# multi-level_converter.net
KiCad netlist of a schematic drawn in EAGLE
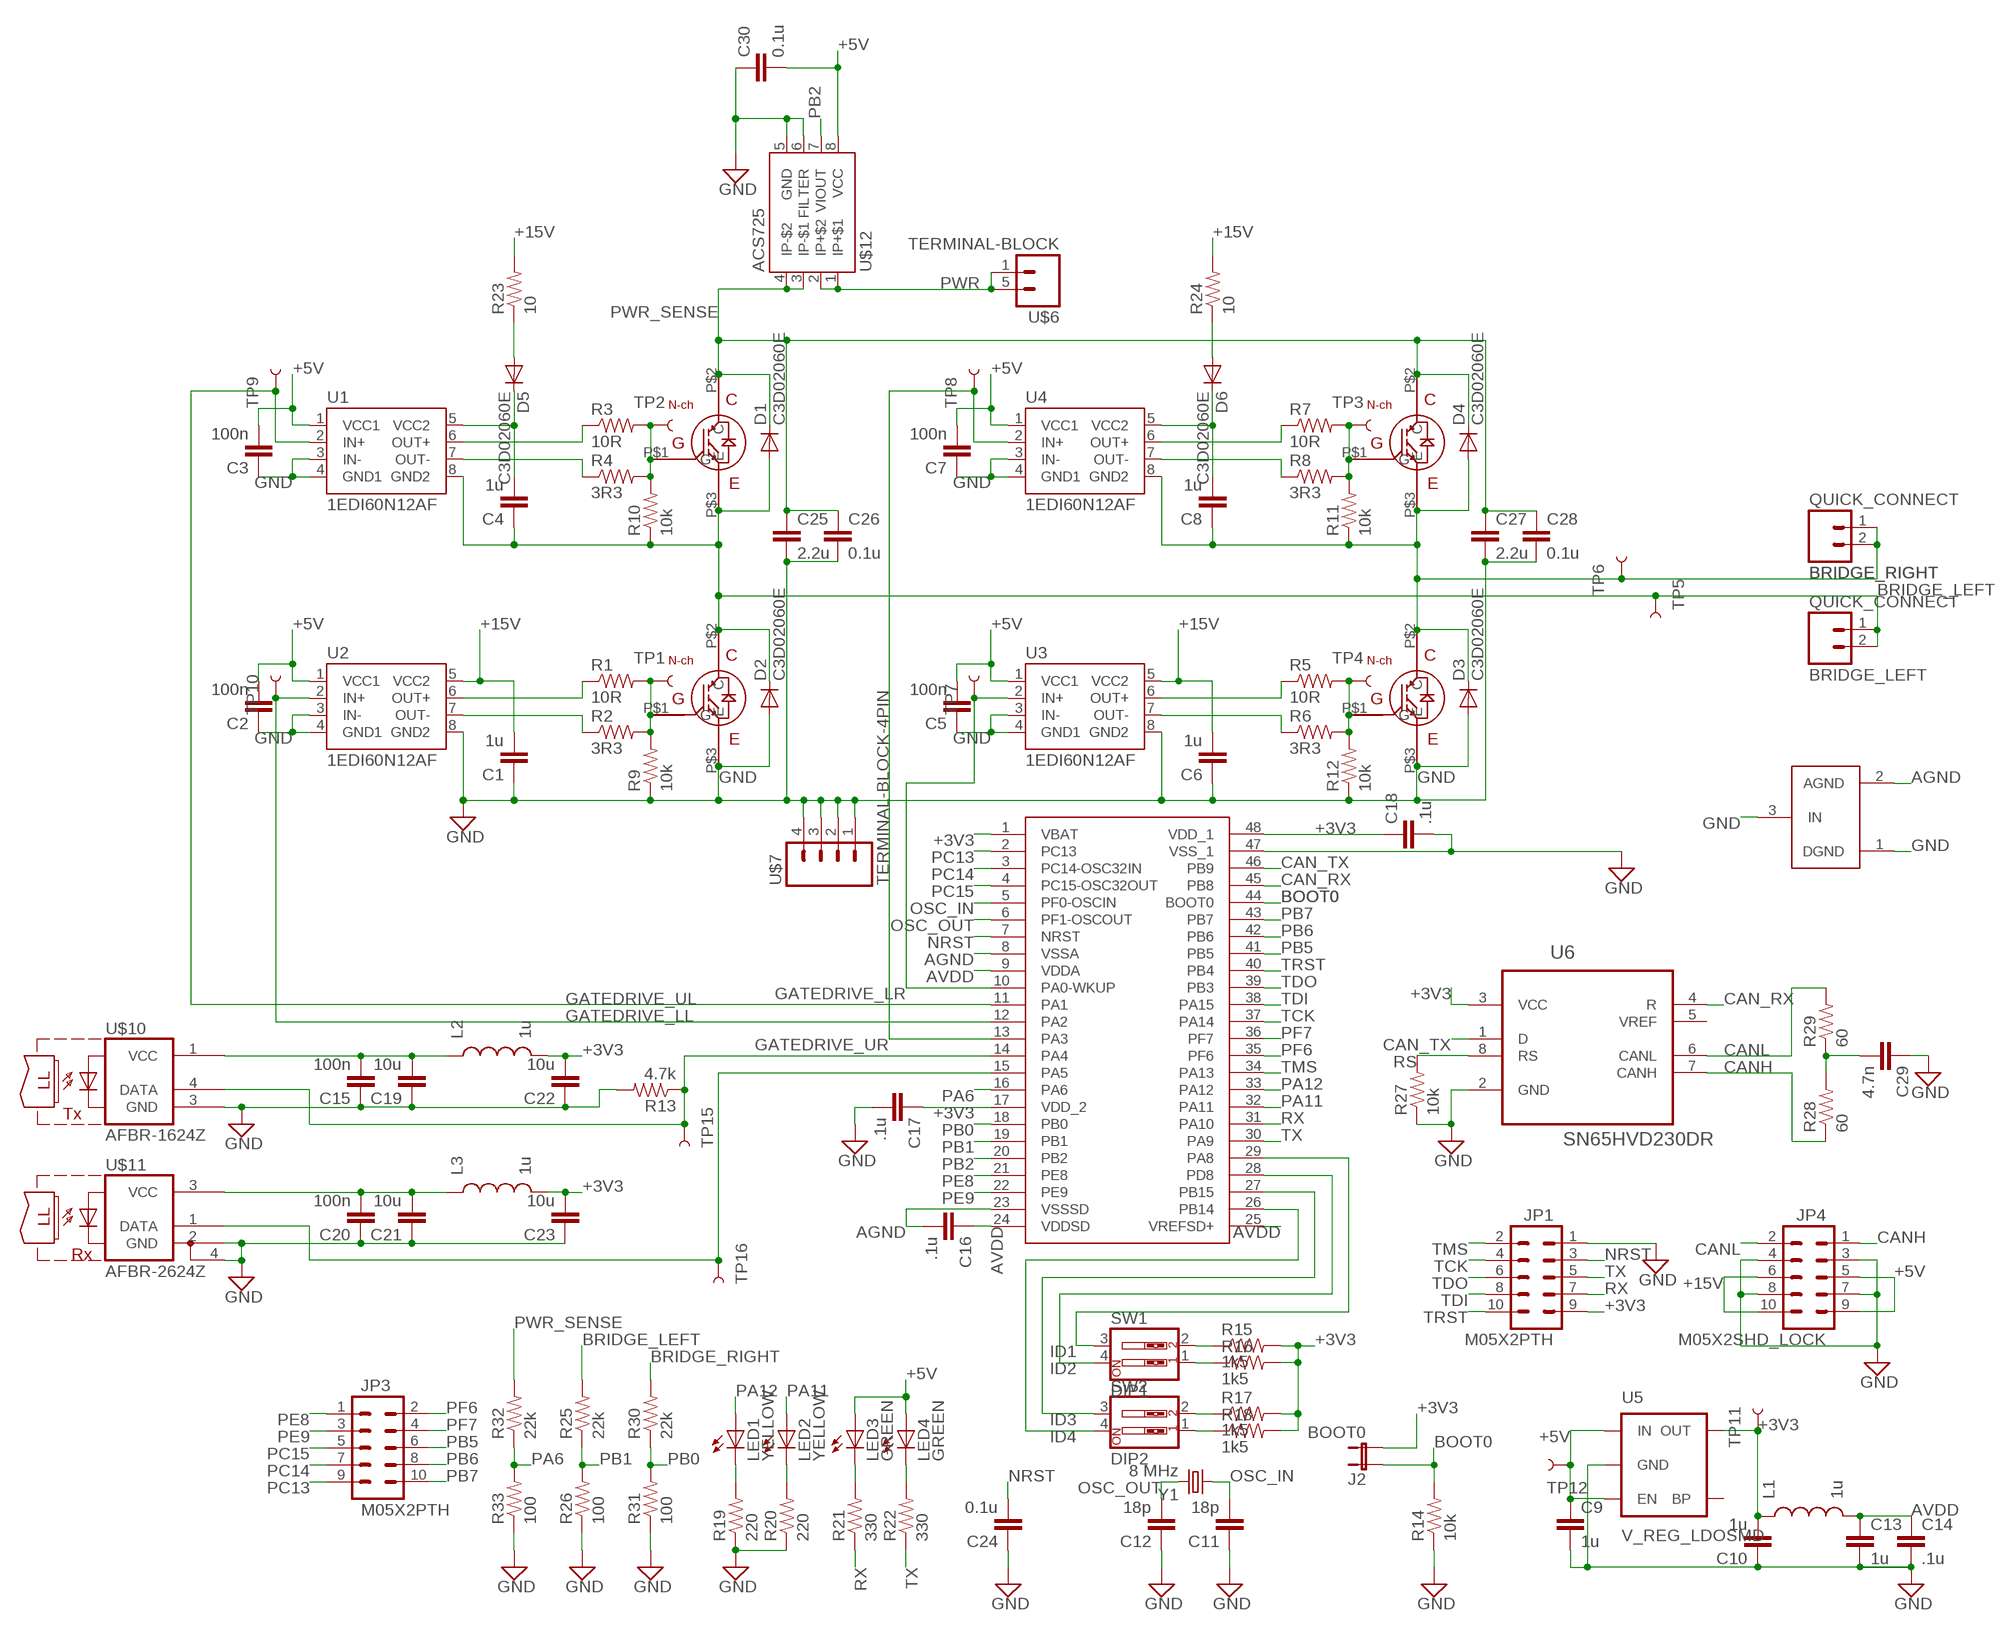
[diagram p0: schematic, sheet 1]

(export (version "E")
  (design (tool "Eeschema 10.0.6"))
  (components
    (comp (ref "BRIDGE_LEFT")
      (value "QUICK_CONNECT")
      (footprint "eagle-import:QUICK_CONNECT")
      (libsource (lib "eagle-import") (part "QUICK_CONNECT"))
    )
    (comp (ref "BRIDGE_RIGHT")
      (value "QUICK_CONNECT")
      (footprint "eagle-import:QUICK_CONNECT")
      (libsource (lib "eagle-import") (part "QUICK_CONNECT"))
    )
    (comp (ref "C1")
      (value "1u")
      (footprint "eagle-import:0805")
      (libsource (lib "eagle-import") (part "CAP0805"))
    )
    (comp (ref "C2")
      (value "100n")
      (footprint "eagle-import:0805")
      (libsource (lib "eagle-import") (part "CAP0805"))
    )
    (comp (ref "C3")
      (value "100n")
      (footprint "eagle-import:0805")
      (libsource (lib "eagle-import") (part "CAP0805"))
    )
    (comp (ref "C4")
      (value "1u")
      (footprint "eagle-import:0805")
      (libsource (lib "eagle-import") (part "CAP0805"))
    )
    (comp (ref "C5")
      (value "100n")
      (footprint "eagle-import:0805")
      (libsource (lib "eagle-import") (part "CAP0805"))
    )
    (comp (ref "C6")
      (value "1u")
      (footprint "eagle-import:0805")
      (libsource (lib "eagle-import") (part "CAP0805"))
    )
    (comp (ref "C7")
      (value "100n")
      (footprint "eagle-import:0805")
      (libsource (lib "eagle-import") (part "CAP0805"))
    )
    (comp (ref "C8")
      (value "1u")
      (footprint "eagle-import:0805")
      (libsource (lib "eagle-import") (part "CAP0805"))
    )
    (comp (ref "C9")
      (value "1u")
      (footprint "eagle-import:0805")
      (libsource (lib "eagle-import") (part "CAP0805"))
    )
    (comp (ref "C10")
      (value "1u")
      (footprint "eagle-import:0805")
      (libsource (lib "eagle-import") (part "CAP0805"))
    )
    (comp (ref "C11")
      (value "18p")
      (footprint "eagle-import:0805")
      (libsource (lib "eagle-import") (part "CAP0805"))
    )
    (comp (ref "C12")
      (value "18p")
      (footprint "eagle-import:0805")
      (libsource (lib "eagle-import") (part "CAP0805"))
    )
    (comp (ref "C13")
      (value "1u")
      (footprint "eagle-import:0805")
      (libsource (lib "eagle-import") (part "CAP0805"))
    )
    (comp (ref "C14")
      (value ".1u")
      (footprint "eagle-import:0805")
      (libsource (lib "eagle-import") (part "CAP0805"))
    )
    (comp (ref "C15")
      (value "100n")
      (footprint "eagle-import:0805")
      (libsource (lib "eagle-import") (part "CAP0805"))
    )
    (comp (ref "C16")
      (value ".1u")
      (footprint "eagle-import:0805")
      (libsource (lib "eagle-import") (part "CAP0805"))
    )
    (comp (ref "C17")
      (value ".1u")
      (footprint "eagle-import:0805")
      (libsource (lib "eagle-import") (part "CAP0805"))
    )
    (comp (ref "C18")
      (value ".1u")
      (footprint "eagle-import:0805")
      (libsource (lib "eagle-import") (part "CAP0805"))
    )
    (comp (ref "C19")
      (value "10u")
      (footprint "eagle-import:0805")
      (libsource (lib "eagle-import") (part "CAP0805"))
    )
    (comp (ref "C20")
      (value "100n")
      (footprint "eagle-import:0805")
      (libsource (lib "eagle-import") (part "CAP0805"))
    )
    (comp (ref "C21")
      (value "10u")
      (footprint "eagle-import:0805")
      (libsource (lib "eagle-import") (part "CAP0805"))
    )
    (comp (ref "C22")
      (value "10u")
      (footprint "eagle-import:0805")
      (libsource (lib "eagle-import") (part "CAP0805"))
    )
    (comp (ref "C23")
      (value "10u")
      (footprint "eagle-import:0805")
      (libsource (lib "eagle-import") (part "CAP0805"))
    )
    (comp (ref "C24")
      (value "0.1u")
      (footprint "eagle-import:0805")
      (libsource (lib "eagle-import") (part "CAP0805"))
    )
    (comp (ref "C25")
      (value "2.2u")
      (footprint "eagle-import:C37.5B20")
      (libsource (lib "eagle-import") (part "C37/20"))
    )
    (comp (ref "C26")
      (value "0.1u")
      (footprint "eagle-import:C2225K")
      (libsource (lib "eagle-import") (part "C-EUC2225K"))
    )
    (comp (ref "C27")
      (value "2.2u")
      (footprint "eagle-import:C37.5B20")
      (libsource (lib "eagle-import") (part "C37/20"))
    )
    (comp (ref "C28")
      (value "0.1u")
      (footprint "eagle-import:C2225K")
      (libsource (lib "eagle-import") (part "C-EUC2225K"))
    )
    (comp (ref "C29")
      (value "4.7n")
      (footprint "eagle-import:0805")
      (libsource (lib "eagle-import") (part "CAP0805"))
    )
    (comp (ref "C30")
      (value "0.1u")
      (footprint "eagle-import:0805")
      (libsource (lib "eagle-import") (part "CAP0805"))
    )
    (comp (ref "D1")
      (value "C3D02060E")
      (footprint "eagle-import:TO252")
      (libsource (lib "eagle-import") (part "C3D02060E"))
    )
    (comp (ref "D2")
      (value "C3D02060E")
      (footprint "eagle-import:TO252")
      (libsource (lib "eagle-import") (part "C3D02060E"))
    )
    (comp (ref "D3")
      (value "C3D02060E")
      (footprint "eagle-import:TO252")
      (libsource (lib "eagle-import") (part "C3D02060E"))
    )
    (comp (ref "D4")
      (value "C3D02060E")
      (footprint "eagle-import:TO252")
      (libsource (lib "eagle-import") (part "C3D02060E"))
    )
    (comp (ref "D5")
      (value "C3D02060E")
      (footprint "eagle-import:TO252")
      (libsource (lib "eagle-import") (part "C3D02060E"))
    )
    (comp (ref "D6")
      (value "C3D02060E")
      (footprint "eagle-import:TO252")
      (libsource (lib "eagle-import") (part "C3D02060E"))
    )
    (comp (ref "J1")
      (value "GND_CONNECT")
      (footprint "eagle-import:GND_CONNECT")
      (libsource (lib "eagle-import") (part "GND_CONNECT"))
    )
    (comp (ref "J2")
      (value "BOOT0")
      (footprint "eagle-import:1X02")
      (libsource (lib "eagle-import") (part "JUMPER-2PTH"))
    )
    (comp (ref "JP1")
      (value "M05X2PTH")
      (footprint "eagle-import:AVR_ICSP")
      (libsource (lib "eagle-import") (part "M05X2PTH"))
    )
    (comp (ref "JP3")
      (value "M05X2PTH")
      (footprint "eagle-import:AVR_ICSP")
      (libsource (lib "eagle-import") (part "M05X2PTH"))
    )
    (comp (ref "JP4")
      (value "M05X2SHD_LOCK")
      (footprint "eagle-import:2X5-SHROUDED_LOCK")
      (libsource (lib "eagle-import") (part "M05X2SHD_LOCK"))
    )
    (comp (ref "L1")
      (value "1u")
      (footprint "eagle-import:0805")
      (libsource (lib "eagle-import") (part "INDUCTOR0805"))
    )
    (comp (ref "L2")
      (value "1u")
      (footprint "eagle-import:0805")
      (libsource (lib "eagle-import") (part "INDUCTOR0805"))
    )
    (comp (ref "L3")
      (value "1u")
      (footprint "eagle-import:0805")
      (libsource (lib "eagle-import") (part "INDUCTOR0805"))
    )
    (comp (ref "LED1")
      (value "YELLOW")
      (footprint "eagle-import:LED-0603")
      (libsource (lib "eagle-import") (part "LED0603"))
    )
    (comp (ref "LED2")
      (value "YELLOW")
      (footprint "eagle-import:LED-0603")
      (libsource (lib "eagle-import") (part "LED0603"))
    )
    (comp (ref "LED3")
      (value "GREEN")
      (footprint "eagle-import:LED-0603")
      (libsource (lib "eagle-import") (part "LED0603"))
    )
    (comp (ref "LED4")
      (value "GREEN")
      (footprint "eagle-import:LED-0603")
      (libsource (lib "eagle-import") (part "LED0603"))
    )
    (comp (ref "R1")
      (value "10R")
      (footprint "eagle-import:0805")
      (libsource (lib "eagle-import") (part "RESISTOR0805-RES"))
    )
    (comp (ref "R2")
      (value "3R3")
      (footprint "eagle-import:0805")
      (libsource (lib "eagle-import") (part "RESISTOR0805-RES"))
    )
    (comp (ref "R3")
      (value "10R")
      (footprint "eagle-import:0805")
      (libsource (lib "eagle-import") (part "RESISTOR0805-RES"))
    )
    (comp (ref "R4")
      (value "3R3")
      (footprint "eagle-import:0805")
      (libsource (lib "eagle-import") (part "RESISTOR0805-RES"))
    )
    (comp (ref "R5")
      (value "10R")
      (footprint "eagle-import:0805")
      (libsource (lib "eagle-import") (part "RESISTOR0805-RES"))
    )
    (comp (ref "R6")
      (value "3R3")
      (footprint "eagle-import:0805")
      (libsource (lib "eagle-import") (part "RESISTOR0805-RES"))
    )
    (comp (ref "R7")
      (value "10R")
      (footprint "eagle-import:0805")
      (libsource (lib "eagle-import") (part "RESISTOR0805-RES"))
    )
    (comp (ref "R8")
      (value "3R3")
      (footprint "eagle-import:0805")
      (libsource (lib "eagle-import") (part "RESISTOR0805-RES"))
    )
    (comp (ref "R9")
      (value "10k")
      (footprint "eagle-import:0805")
      (libsource (lib "eagle-import") (part "RESISTOR0805-RES"))
    )
    (comp (ref "R10")
      (value "10k")
      (footprint "eagle-import:0805")
      (libsource (lib "eagle-import") (part "RESISTOR0805-RES"))
    )
    (comp (ref "R11")
      (value "10k")
      (footprint "eagle-import:0805")
      (libsource (lib "eagle-import") (part "RESISTOR0805-RES"))
    )
    (comp (ref "R12")
      (value "10k")
      (footprint "eagle-import:0805")
      (libsource (lib "eagle-import") (part "RESISTOR0805-RES"))
    )
    (comp (ref "R13")
      (value "4.7k")
      (footprint "eagle-import:0805")
      (libsource (lib "eagle-import") (part "RESISTOR0805-RES"))
    )
    (comp (ref "R14")
      (value "10k")
      (footprint "eagle-import:0805")
      (libsource (lib "eagle-import") (part "RESISTOR0805-RES"))
    )
    (comp (ref "R15")
      (value "1k5")
      (footprint "eagle-import:0805")
      (libsource (lib "eagle-import") (part "RESISTOR0805-RES"))
    )
    (comp (ref "R16")
      (value "1k5")
      (footprint "eagle-import:0805")
      (libsource (lib "eagle-import") (part "RESISTOR0805-RES"))
    )
    (comp (ref "R17")
      (value "1k5")
      (footprint "eagle-import:0805")
      (libsource (lib "eagle-import") (part "RESISTOR0805-RES"))
    )
    (comp (ref "R18")
      (value "1k5")
      (footprint "eagle-import:0805")
      (libsource (lib "eagle-import") (part "RESISTOR0805-RES"))
    )
    (comp (ref "R19")
      (value "220")
      (footprint "eagle-import:0805")
      (libsource (lib "eagle-import") (part "RESISTOR0805-RES"))
    )
    (comp (ref "R20")
      (value "220")
      (footprint "eagle-import:0805")
      (libsource (lib "eagle-import") (part "RESISTOR0805-RES"))
    )
    (comp (ref "R21")
      (value "330")
      (footprint "eagle-import:0805")
      (libsource (lib "eagle-import") (part "RESISTOR0805-RES"))
    )
    (comp (ref "R22")
      (value "330")
      (footprint "eagle-import:0805")
      (libsource (lib "eagle-import") (part "RESISTOR0805-RES"))
    )
    (comp (ref "R23")
      (value "10")
      (footprint "eagle-import:0805")
      (libsource (lib "eagle-import") (part "RESISTOR0805-RES"))
    )
    (comp (ref "R24")
      (value "10")
      (footprint "eagle-import:0805")
      (libsource (lib "eagle-import") (part "RESISTOR0805-RES"))
    )
    (comp (ref "R25")
      (value "22k")
      (footprint "eagle-import:0805")
      (libsource (lib "eagle-import") (part "RESISTOR0805-RES"))
    )
    (comp (ref "R26")
      (value "100")
      (footprint "eagle-import:0805")
      (libsource (lib "eagle-import") (part "RESISTOR0805-RES"))
    )
    (comp (ref "R27")
      (value "10k")
      (footprint "eagle-import:0805")
      (libsource (lib "eagle-import") (part "RESISTOR0805-RES"))
    )
    (comp (ref "R28")
      (value "60")
      (footprint "eagle-import:0805")
      (libsource (lib "eagle-import") (part "RESISTOR0805-RES"))
    )
    (comp (ref "R29")
      (value "60")
      (footprint "eagle-import:0805")
      (libsource (lib "eagle-import") (part "RESISTOR0805-RES"))
    )
    (comp (ref "R30")
      (value "22k")
      (footprint "eagle-import:0805")
      (libsource (lib "eagle-import") (part "RESISTOR0805-RES"))
    )
    (comp (ref "R31")
      (value "100")
      (footprint "eagle-import:0805")
      (libsource (lib "eagle-import") (part "RESISTOR0805-RES"))
    )
    (comp (ref "R32")
      (value "22k")
      (footprint "eagle-import:0805")
      (libsource (lib "eagle-import") (part "RESISTOR0805-RES"))
    )
    (comp (ref "R33")
      (value "100")
      (footprint "eagle-import:0805")
      (libsource (lib "eagle-import") (part "RESISTOR0805-RES"))
    )
    (comp (ref "SW1")
      (value "DIP1")
      (footprint "eagle-import:DIPSWITCH-02")
      (libsource (lib "eagle-import") (part "SW_DIP-2"))
    )
    (comp (ref "SW2")
      (value "DIP2")
      (footprint "eagle-import:DIPSWITCH-02")
      (libsource (lib "eagle-import") (part "SW_DIP-2"))
    )
    (comp (ref "TP1")
      (value "TEST-POINT3X5")
      (footprint "eagle-import:PAD.03X.05")
      (libsource (lib "eagle-import") (part "TEST-POINT3X5"))
    )
    (comp (ref "TP2")
      (value "TEST-POINT3X5")
      (footprint "eagle-import:PAD.03X.05")
      (libsource (lib "eagle-import") (part "TEST-POINT3X5"))
    )
    (comp (ref "TP3")
      (value "TEST-POINT3X5")
      (footprint "eagle-import:PAD.03X.05")
      (libsource (lib "eagle-import") (part "TEST-POINT3X5"))
    )
    (comp (ref "TP4")
      (value "TEST-POINT3X5")
      (footprint "eagle-import:PAD.03X.05")
      (libsource (lib "eagle-import") (part "TEST-POINT3X5"))
    )
    (comp (ref "TP5")
      (value "TEST-POINT3X5")
      (footprint "eagle-import:PAD.03X.05")
      (libsource (lib "eagle-import") (part "TEST-POINT3X5"))
    )
    (comp (ref "TP6")
      (value "TEST-POINT3X5")
      (footprint "eagle-import:PAD.03X.05")
      (libsource (lib "eagle-import") (part "TEST-POINT3X5"))
    )
    (comp (ref "TP7")
      (value "TEST-POINT3X5")
      (footprint "eagle-import:PAD.03X.05")
      (libsource (lib "eagle-import") (part "TEST-POINT3X5"))
    )
    (comp (ref "TP8")
      (value "TEST-POINT3X5")
      (footprint "eagle-import:PAD.03X.05")
      (libsource (lib "eagle-import") (part "TEST-POINT3X5"))
    )
    (comp (ref "TP9")
      (value "TEST-POINT3X5")
      (footprint "eagle-import:PAD.03X.05")
      (libsource (lib "eagle-import") (part "TEST-POINT3X5"))
    )
    (comp (ref "TP10")
      (value "TEST-POINT3X5")
      (footprint "eagle-import:PAD.03X.05")
      (libsource (lib "eagle-import") (part "TEST-POINT3X5"))
    )
    (comp (ref "TP11")
      (value "TEST-POINT3X5")
      (footprint "eagle-import:PAD.03X.05")
      (libsource (lib "eagle-import") (part "TEST-POINT3X5"))
    )
    (comp (ref "TP12")
      (value "TEST-POINT3X5")
      (footprint "eagle-import:PAD.03X.05")
      (libsource (lib "eagle-import") (part "TEST-POINT3X5"))
    )
    (comp (ref "TP15")
      (value "TEST-POINT3X5")
      (footprint "eagle-import:PAD.03X.05")
      (libsource (lib "eagle-import") (part "TEST-POINT3X5"))
    )
    (comp (ref "TP16")
      (value "TEST-POINT3X5")
      (footprint "eagle-import:PAD.03X.05")
      (libsource (lib "eagle-import") (part "TEST-POINT3X5"))
    )
    (comp (ref "U$1")
      (value "TO-247B")
      (footprint "eagle-import:TO-247-FLAT")
      (libsource (lib "eagle-import") (part "TO-247B"))
    )
    (comp (ref "U$2")
      (value "TO-247B")
      (footprint "eagle-import:TO-247-FLAT")
      (libsource (lib "eagle-import") (part "TO-247B"))
    )
    (comp (ref "U$3")
      (value "TO-247B")
      (footprint "eagle-import:TO-247-FLAT")
      (libsource (lib "eagle-import") (part "TO-247B"))
    )
    (comp (ref "U$4")
      (value "TO-247B")
      (footprint "eagle-import:TO-247-FLAT")
      (libsource (lib "eagle-import") (part "TO-247B"))
    )
    (comp (ref "U$5")
      (value "STM32F373CCT6")
      (footprint "eagle-import:LQFP48")
      (libsource (lib "eagle-import") (part "STM32F373CCT6"))
    )
    (comp (ref "U$6")
      (value "TERMINAL-BLOCK")
      (footprint "eagle-import:10MM_2PIN_CONNECTOR")
      (libsource (lib "eagle-import") (part "TERMINAL-BLOCK"))
    )
    (comp (ref "U$7")
      (value "TERMINAL-BLOCK-4PIN")
      (footprint "eagle-import:10MM_4PIN_CONNECTOR")
      (libsource (lib "eagle-import") (part "TERMINAL-BLOCK-4PIN"))
    )
    (comp (ref "U$10")
      (value "AFBR-1624Z")
      (footprint "eagle-import:HFBR-15X3")
      (libsource (lib "eagle-import") (part "AFBR-1624Z"))
    )
    (comp (ref "U$11")
      (value "AFBR-2624Z")
      (footprint "eagle-import:HFBR-15X3")
      (libsource (lib "eagle-import") (part "AFBR-2624Z"))
    )
    (comp (ref "U$12")
      (value "ACS725")
      (footprint "eagle-import:SO08")
      (libsource (lib "eagle-import") (part "ACS725"))
    )
    (comp (ref "U1")
      (value "1EDI60N12AF")
      (footprint "eagle-import:SO08")
      (libsource (lib "eagle-import") (part "1EDI60N12AF"))
    )
    (comp (ref "U2")
      (value "1EDI60N12AF")
      (footprint "eagle-import:SO08")
      (libsource (lib "eagle-import") (part "1EDI60N12AF"))
    )
    (comp (ref "U3")
      (value "1EDI60N12AF")
      (footprint "eagle-import:SO08")
      (libsource (lib "eagle-import") (part "1EDI60N12AF"))
    )
    (comp (ref "U4")
      (value "1EDI60N12AF")
      (footprint "eagle-import:SO08")
      (libsource (lib "eagle-import") (part "1EDI60N12AF"))
    )
    (comp (ref "U5")
      (value "V_REG_LDOSMD")
      (footprint "eagle-import:SOT23-5")
      (libsource (lib "eagle-import") (part "V_REG_LDOSMD"))
    )
    (comp (ref "U6")
      (value "SN65HVD230DR")
      (footprint "eagle-import:SOIC127P600X175-8N")
      (libsource (lib "eagle-import") (part "SN65HVD230DR"))
    )
    (comp (ref "Y1")
      (value "8 MHz")
      (footprint "eagle-import:HC49UP")
      (libsource (lib "eagle-import") (part "CRYSTALSMD"))
    )
  )
  (nets
    (net (code "1") (name "/+3V3") (class "Default")
      (node (ref "C10") (pin "2") (pinfunction "2_2") (pintype "passive"))
      (node (ref "C17") (pin "1") (pinfunction "1_1") (pintype "passive"))
      (node (ref "C18") (pin "1") (pinfunction "1_1") (pintype "passive"))
      (node (ref "C22") (pin "2") (pinfunction "2_2") (pintype "passive"))
      (node (ref "C23") (pin "2") (pinfunction "2_2") (pintype "passive"))
      (node (ref "J2") (pin "2") (pinfunction "2_2") (pintype "passive"))
      (node (ref "JP1") (pin "9") (pinfunction "9_9") (pintype "passive"))
      (node (ref "L1") (pin "1") (pinfunction "1_1") (pintype "passive"))
      (node (ref "L2") (pin "2") (pinfunction "2_2") (pintype "passive"))
      (node (ref "L3") (pin "2") (pinfunction "2_2") (pintype "passive"))
      (node (ref "R15") (pin "2") (pinfunction "2_2") (pintype "passive"))
      (node (ref "R16") (pin "2") (pinfunction "2_2") (pintype "passive"))
      (node (ref "R17") (pin "2") (pinfunction "2_2") (pintype "passive"))
      (node (ref "R18") (pin "2") (pinfunction "2_2") (pintype "passive"))
      (node (ref "TP11") (pin "P$1") (pinfunction "1_P$1") (pintype "bidirectional"))
      (node (ref "U$5") (pin "1") (pinfunction "VBAT_1") (pintype "bidirectional"))
      (node (ref "U$5") (pin "17") (pinfunction "VDD_2_17") (pintype "bidirectional"))
      (node (ref "U$5") (pin "48") (pinfunction "VDD_1_48") (pintype "bidirectional"))
      (node (ref "U5") (pin "VS") (pinfunction "OUT_VS") (pintype "passive"))
      (node (ref "U6") (pin "3") (pinfunction "VCC_3") (pintype "power_in"))
    )
    (net (code "2") (name "/+5V") (class "Default")
      (node (ref "C2") (pin "2") (pinfunction "2_2") (pintype "passive"))
      (node (ref "C3") (pin "2") (pinfunction "2_2") (pintype "passive"))
      (node (ref "C30") (pin "2") (pinfunction "2_2") (pintype "passive"))
      (node (ref "C5") (pin "2") (pinfunction "2_2") (pintype "passive"))
      (node (ref "C7") (pin "2") (pinfunction "2_2") (pintype "passive"))
      (node (ref "C9") (pin "1") (pinfunction "1_1") (pintype "passive"))
      (node (ref "JP4") (pin "5") (pinfunction "5_5") (pintype "passive"))
      (node (ref "JP4") (pin "9") (pinfunction "9_9") (pintype "passive"))
      (node (ref "LED3") (pin "A") (pinfunction "A_A") (pintype "passive"))
      (node (ref "LED4") (pin "A") (pinfunction "A_A") (pintype "passive"))
      (node (ref "TP12") (pin "P$1") (pinfunction "1_P$1") (pintype "bidirectional"))
      (node (ref "U$12") (pin "8") (pinfunction "VCC_8") (pintype "bidirectional"))
      (node (ref "U1") (pin "1") (pinfunction "VCC1_1") (pintype "bidirectional"))
      (node (ref "U2") (pin "1") (pinfunction "VCC1_1") (pintype "bidirectional"))
      (node (ref "U3") (pin "1") (pinfunction "VCC1_1") (pintype "bidirectional"))
      (node (ref "U4") (pin "1") (pinfunction "VCC1_1") (pintype "bidirectional"))
      (node (ref "U5") (pin "CS") (pinfunction "IN_CS") (pintype "input"))
      (node (ref "U5") (pin "GATE") (pinfunction "EN_GATE") (pintype "input"))
    )
    (net (code "3") (name "/+15V") (class "Default")
      (node (ref "C1") (pin "2") (pinfunction "2_2") (pintype "passive"))
      (node (ref "C6") (pin "2") (pinfunction "2_2") (pintype "passive"))
      (node (ref "JP4") (pin "10") (pinfunction "10_10") (pintype "passive"))
      (node (ref "JP4") (pin "6") (pinfunction "6_6") (pintype "passive"))
      (node (ref "R23") (pin "2") (pinfunction "2_2") (pintype "passive"))
      (node (ref "R24") (pin "2") (pinfunction "2_2") (pintype "passive"))
      (node (ref "U2") (pin "5") (pinfunction "VCC2_5") (pintype "bidirectional"))
      (node (ref "U3") (pin "5") (pinfunction "VCC2_5") (pintype "bidirectional"))
    )
    (net (code "4") (name "/AGND") (class "Default")
      (node (ref "C16") (pin "2") (pinfunction "2_2") (pintype "passive"))
      (node (ref "J1") (pin "2") (pinfunction "AGND_2") (pintype "bidirectional"))
      (node (ref "U$5") (pin "23") (pinfunction "VSSSD_23") (pintype "bidirectional"))
      (node (ref "U$5") (pin "8") (pinfunction "VSSA_8") (pintype "bidirectional"))
    )
    (net (code "5") (name "/AVDD") (class "Default")
      (node (ref "C13") (pin "1") (pinfunction "1_1") (pintype "passive"))
      (node (ref "C14") (pin "1") (pinfunction "1_1") (pintype "passive"))
      (node (ref "C16") (pin "1") (pinfunction "1_1") (pintype "passive"))
      (node (ref "L1") (pin "2") (pinfunction "2_2") (pintype "passive"))
      (node (ref "U$5") (pin "24") (pinfunction "VDDSD_24") (pintype "bidirectional"))
      (node (ref "U$5") (pin "25") (pinfunction "VREFSD+_25") (pintype "bidirectional"))
      (node (ref "U$5") (pin "9") (pinfunction "VDDA_9") (pintype "bidirectional"))
    )
    (net (code "6") (name "/BOOT0") (class "Default")
      (node (ref "J2") (pin "1") (pinfunction "1_1") (pintype "passive"))
      (node (ref "R14") (pin "2") (pinfunction "2_2") (pintype "passive"))
      (node (ref "U$5") (pin "44") (pinfunction "BOOT0_44") (pintype "bidirectional"))
    )
    (net (code "7") (name "/BRIDGE_LEFT") (class "Default")
      (node (ref "BRIDGE_LEFT") (pin "1") (pinfunction "1_1") (pintype "passive"))
      (node (ref "BRIDGE_LEFT") (pin "2") (pinfunction "2_2") (pintype "passive"))
      (node (ref "C4") (pin "1") (pinfunction "1_1") (pintype "passive"))
      (node (ref "D1") (pin "2") (pinfunction "A_2") (pintype "passive"))
      (node (ref "D2") (pin "1") (pinfunction "C_1") (pintype "passive"))
      (node (ref "D2") (pin "3") (pinfunction "C_3") (pintype "passive"))
      (node (ref "R10") (pin "1") (pinfunction "1_1") (pintype "passive"))
      (node (ref "R25") (pin "2") (pinfunction "2_2") (pintype "passive"))
      (node (ref "TP5") (pin "P$1") (pinfunction "1_P$1") (pintype "bidirectional"))
      (node (ref "U$1") (pin "P$3") (pinfunction "E_P$3") (pintype "bidirectional"))
      (node (ref "U$3") (pin "P$2") (pinfunction "C_P$2") (pintype "bidirectional"))
      (node (ref "U1") (pin "8") (pinfunction "GND2_8") (pintype "bidirectional"))
    )
    (net (code "8") (name "/BRIDGE_RIGHT") (class "Default")
      (node (ref "BRIDGE_RIGHT") (pin "1") (pinfunction "1_1") (pintype "passive"))
      (node (ref "BRIDGE_RIGHT") (pin "2") (pinfunction "2_2") (pintype "passive"))
      (node (ref "C8") (pin "1") (pinfunction "1_1") (pintype "passive"))
      (node (ref "D3") (pin "1") (pinfunction "C_1") (pintype "passive"))
      (node (ref "D3") (pin "3") (pinfunction "C_3") (pintype "passive"))
      (node (ref "D4") (pin "2") (pinfunction "A_2") (pintype "passive"))
      (node (ref "R11") (pin "1") (pinfunction "1_1") (pintype "passive"))
      (node (ref "R30") (pin "2") (pinfunction "2_2") (pintype "passive"))
      (node (ref "TP6") (pin "P$1") (pinfunction "1_P$1") (pintype "bidirectional"))
      (node (ref "U$2") (pin "P$2") (pinfunction "C_P$2") (pintype "bidirectional"))
      (node (ref "U$4") (pin "P$3") (pinfunction "E_P$3") (pintype "bidirectional"))
      (node (ref "U4") (pin "8") (pinfunction "GND2_8") (pintype "bidirectional"))
    )
    (net (code "9") (name "/CANH") (class "Default")
      (node (ref "JP4") (pin "1") (pinfunction "1_1") (pintype "passive"))
      (node (ref "R28") (pin "1") (pinfunction "1_1") (pintype "passive"))
      (node (ref "U6") (pin "7") (pinfunction "CANH_7") (pintype "output"))
    )
    (net (code "10") (name "/CANL") (class "Default")
      (node (ref "JP4") (pin "2") (pinfunction "2_2") (pintype "passive"))
      (node (ref "R29") (pin "2") (pinfunction "2_2") (pintype "passive"))
      (node (ref "U6") (pin "6") (pinfunction "CANL_6") (pintype "output"))
    )
    (net (code "11") (name "/CAN_RX") (class "Default")
      (node (ref "U$5") (pin "45") (pinfunction "PB8_45") (pintype "bidirectional"))
      (node (ref "U6") (pin "4") (pinfunction "R_4") (pintype "output"))
    )
    (net (code "12") (name "/CAN_TX") (class "Default")
      (node (ref "U$5") (pin "46") (pinfunction "PB9_46") (pintype "bidirectional"))
      (node (ref "U6") (pin "1") (pinfunction "D_1") (pintype "input"))
    )
    (net (code "13") (name "/GATEDRIVE_LL") (class "Default")
      (node (ref "TP10") (pin "P$1") (pinfunction "1_P$1") (pintype "bidirectional"))
      (node (ref "U$5") (pin "12") (pinfunction "PA2_12") (pintype "bidirectional"))
      (node (ref "U2") (pin "2") (pinfunction "IN+_2") (pintype "bidirectional"))
    )
    (net (code "14") (name "/GATEDRIVE_LR") (class "Default")
      (node (ref "TP7") (pin "P$1") (pinfunction "1_P$1") (pintype "bidirectional"))
      (node (ref "U$5") (pin "10") (pinfunction "PA0-WKUP_10") (pintype "bidirectional"))
      (node (ref "U3") (pin "2") (pinfunction "IN+_2") (pintype "bidirectional"))
    )
    (net (code "15") (name "/GATEDRIVE_UL") (class "Default")
      (node (ref "TP9") (pin "P$1") (pinfunction "1_P$1") (pintype "bidirectional"))
      (node (ref "U$5") (pin "11") (pinfunction "PA1_11") (pintype "bidirectional"))
      (node (ref "U1") (pin "2") (pinfunction "IN+_2") (pintype "bidirectional"))
    )
    (net (code "16") (name "/GATEDRIVE_UR") (class "Default")
      (node (ref "TP8") (pin "P$1") (pinfunction "1_P$1") (pintype "bidirectional"))
      (node (ref "U$5") (pin "13") (pinfunction "PA3_13") (pintype "bidirectional"))
      (node (ref "U4") (pin "2") (pinfunction "IN+_2") (pintype "bidirectional"))
    )
    (net (code "17") (name "/ID1") (class "Default")
      (node (ref "SW1") (pin "3") (pinfunction "3_3") (pintype "passive"))
      (node (ref "U$5") (pin "29") (pinfunction "PA8_29") (pintype "bidirectional"))
    )
    (net (code "18") (name "/ID2") (class "Default")
      (node (ref "SW1") (pin "4") (pinfunction "4_4") (pintype "passive"))
      (node (ref "U$5") (pin "28") (pinfunction "PD8_28") (pintype "bidirectional"))
    )
    (net (code "19") (name "/ID3") (class "Default")
      (node (ref "SW2") (pin "3") (pinfunction "3_3") (pintype "passive"))
      (node (ref "U$5") (pin "27") (pinfunction "PB15_27") (pintype "bidirectional"))
    )
    (net (code "20") (name "/ID4") (class "Default")
      (node (ref "SW2") (pin "4") (pinfunction "4_4") (pintype "passive"))
      (node (ref "U$5") (pin "26") (pinfunction "PB14_26") (pintype "bidirectional"))
    )
    (net (code "21") (name "/NRST") (class "Default")
      (node (ref "C24") (pin "2") (pinfunction "2_2") (pintype "passive"))
      (node (ref "JP1") (pin "3") (pinfunction "3_3") (pintype "passive"))
      (node (ref "U$5") (pin "7") (pinfunction "NRST_7") (pintype "bidirectional"))
    )
    (net (code "22") (name "/OSC_IN") (class "Default")
      (node (ref "C11") (pin "2") (pinfunction "2_2") (pintype "passive"))
      (node (ref "U$5") (pin "5") (pinfunction "PF0-OSCIN_5") (pintype "bidirectional"))
      (node (ref "Y1") (pin "1") (pinfunction "1_1") (pintype "passive"))
    )
    (net (code "23") (name "/OSC_OUT") (class "Default")
      (node (ref "C12") (pin "2") (pinfunction "2_2") (pintype "passive"))
      (node (ref "U$5") (pin "6") (pinfunction "PF1-OSCOUT_6") (pintype "bidirectional"))
      (node (ref "Y1") (pin "2") (pinfunction "2_2") (pintype "passive"))
    )
    (net (code "24") (name "/PA6") (class "Default")
      (node (ref "R32") (pin "1") (pinfunction "1_1") (pintype "passive"))
      (node (ref "R33") (pin "2") (pinfunction "2_2") (pintype "passive"))
      (node (ref "U$5") (pin "16") (pinfunction "PA6_16") (pintype "bidirectional"))
    )
    (net (code "25") (name "/PA11") (class "Default")
      (node (ref "LED2") (pin "A") (pinfunction "A_A") (pintype "passive"))
      (node (ref "U$5") (pin "32") (pinfunction "PA11_32") (pintype "bidirectional"))
    )
    (net (code "26") (name "/PA12") (class "Default")
      (node (ref "LED1") (pin "A") (pinfunction "A_A") (pintype "passive"))
      (node (ref "U$5") (pin "33") (pinfunction "PA12_33") (pintype "bidirectional"))
    )
    (net (code "27") (name "/PB0") (class "Default")
      (node (ref "R30") (pin "1") (pinfunction "1_1") (pintype "passive"))
      (node (ref "R31") (pin "2") (pinfunction "2_2") (pintype "passive"))
      (node (ref "U$5") (pin "18") (pinfunction "PB0_18") (pintype "bidirectional"))
    )
    (net (code "28") (name "/PB1") (class "Default")
      (node (ref "R25") (pin "1") (pinfunction "1_1") (pintype "passive"))
      (node (ref "R26") (pin "2") (pinfunction "2_2") (pintype "passive"))
      (node (ref "U$5") (pin "19") (pinfunction "PB1_19") (pintype "bidirectional"))
    )
    (net (code "29") (name "/PB2") (class "Default")
      (node (ref "U$12") (pin "7") (pinfunction "VIOUT_7") (pintype "bidirectional"))
      (node (ref "U$5") (pin "20") (pinfunction "PB2_20") (pintype "bidirectional"))
    )
    (net (code "30") (name "/PB5") (class "Default")
      (node (ref "JP3") (pin "6") (pinfunction "6_6") (pintype "passive"))
      (node (ref "U$5") (pin "41") (pinfunction "PB5_41") (pintype "bidirectional"))
    )
    (net (code "31") (name "/PB6") (class "Default")
      (node (ref "JP3") (pin "8") (pinfunction "8_8") (pintype "passive"))
      (node (ref "U$5") (pin "42") (pinfunction "PB6_42") (pintype "bidirectional"))
    )
    (net (code "32") (name "/PB7") (class "Default")
      (node (ref "JP3") (pin "10") (pinfunction "10_10") (pintype "passive"))
      (node (ref "U$5") (pin "43") (pinfunction "PB7_43") (pintype "bidirectional"))
    )
    (net (code "33") (name "/PC13") (class "Default")
      (node (ref "JP3") (pin "9") (pinfunction "9_9") (pintype "passive"))
      (node (ref "U$5") (pin "2") (pinfunction "PC13_2") (pintype "bidirectional"))
    )
    (net (code "34") (name "/PC14") (class "Default")
      (node (ref "JP3") (pin "7") (pinfunction "7_7") (pintype "passive"))
      (node (ref "U$5") (pin "3") (pinfunction "PC14-OSC32IN_3") (pintype "bidirectional"))
    )
    (net (code "35") (name "/PC15") (class "Default")
      (node (ref "JP3") (pin "5") (pinfunction "5_5") (pintype "passive"))
      (node (ref "U$5") (pin "4") (pinfunction "PC15-OSC32OUT_4") (pintype "bidirectional"))
    )
    (net (code "36") (name "/PE8") (class "Default")
      (node (ref "JP3") (pin "1") (pinfunction "1_1") (pintype "passive"))
      (node (ref "U$5") (pin "21") (pinfunction "PE8_21") (pintype "bidirectional"))
    )
    (net (code "37") (name "/PE9") (class "Default")
      (node (ref "JP3") (pin "3") (pinfunction "3_3") (pintype "passive"))
      (node (ref "U$5") (pin "22") (pinfunction "PE9_22") (pintype "bidirectional"))
    )
    (net (code "38") (name "/PF6") (class "Default")
      (node (ref "JP3") (pin "2") (pinfunction "2_2") (pintype "passive"))
      (node (ref "U$5") (pin "35") (pinfunction "PF6_35") (pintype "bidirectional"))
    )
    (net (code "39") (name "/PF7") (class "Default")
      (node (ref "JP3") (pin "4") (pinfunction "4_4") (pintype "passive"))
      (node (ref "U$5") (pin "36") (pinfunction "PF7_36") (pintype "bidirectional"))
    )
    (net (code "40") (name "/PWR") (class "Default")
      (node (ref "U$12") (pin "1") (pinfunction "IP+$1_1") (pintype "bidirectional"))
      (node (ref "U$12") (pin "2") (pinfunction "IP+$2_2") (pintype "bidirectional"))
      (node (ref "U$6") (pin "1") (pinfunction "1_1") (pintype "passive"))
      (node (ref "U$6") (pin "5") (pinfunction "2_5") (pintype "passive"))
    )
    (net (code "41") (name "/PWR_SENSE") (class "Default")
      (node (ref "C25") (pin "1") (pinfunction "1_1") (pintype "passive"))
      (node (ref "C26") (pin "1") (pinfunction "1_1") (pintype "passive"))
      (node (ref "C27") (pin "1") (pinfunction "1_1") (pintype "passive"))
      (node (ref "C28") (pin "1") (pinfunction "1_1") (pintype "passive"))
      (node (ref "D1") (pin "1") (pinfunction "C_1") (pintype "passive"))
      (node (ref "D1") (pin "3") (pinfunction "C_3") (pintype "passive"))
      (node (ref "D4") (pin "1") (pinfunction "C_1") (pintype "passive"))
      (node (ref "D4") (pin "3") (pinfunction "C_3") (pintype "passive"))
      (node (ref "R32") (pin "2") (pinfunction "2_2") (pintype "passive"))
      (node (ref "U$1") (pin "P$2") (pinfunction "C_P$2") (pintype "bidirectional"))
      (node (ref "U$12") (pin "3") (pinfunction "IP-$1_3") (pintype "bidirectional"))
      (node (ref "U$12") (pin "4") (pinfunction "IP-$2_4") (pintype "bidirectional"))
      (node (ref "U$4") (pin "P$2") (pinfunction "C_P$2") (pintype "bidirectional"))
    )
    (net (code "42") (name "/RS") (class "Default")
      (node (ref "R27") (pin "2") (pinfunction "2_2") (pintype "passive"))
      (node (ref "U6") (pin "8") (pinfunction "RS_8") (pintype "input"))
    )
    (net (code "43") (name "/RX") (class "Default")
      (node (ref "JP1") (pin "7") (pinfunction "7_7") (pintype "passive"))
      (node (ref "R21") (pin "1") (pinfunction "1_1") (pintype "passive"))
      (node (ref "U$5") (pin "31") (pinfunction "PA10_31") (pintype "bidirectional"))
    )
    (net (code "44") (name "/TCK") (class "Default")
      (node (ref "JP1") (pin "4") (pinfunction "4_4") (pintype "passive"))
      (node (ref "U$5") (pin "37") (pinfunction "PA14_37") (pintype "bidirectional"))
    )
    (net (code "45") (name "/TDI") (class "Default")
      (node (ref "JP1") (pin "8") (pinfunction "8_8") (pintype "passive"))
      (node (ref "U$5") (pin "38") (pinfunction "PA15_38") (pintype "bidirectional"))
    )
    (net (code "46") (name "/TDO") (class "Default")
      (node (ref "JP1") (pin "6") (pinfunction "6_6") (pintype "passive"))
      (node (ref "U$5") (pin "39") (pinfunction "PB3_39") (pintype "bidirectional"))
    )
    (net (code "47") (name "/TMS") (class "Default")
      (node (ref "JP1") (pin "2") (pinfunction "2_2") (pintype "passive"))
      (node (ref "U$5") (pin "34") (pinfunction "PA13_34") (pintype "bidirectional"))
    )
    (net (code "48") (name "/TRST") (class "Default")
      (node (ref "JP1") (pin "10") (pinfunction "10_10") (pintype "passive"))
      (node (ref "U$5") (pin "40") (pinfunction "PB4_40") (pintype "bidirectional"))
    )
    (net (code "49") (name "/TX") (class "Default")
      (node (ref "JP1") (pin "5") (pinfunction "5_5") (pintype "passive"))
      (node (ref "R22") (pin "1") (pinfunction "1_1") (pintype "passive"))
      (node (ref "U$5") (pin "30") (pinfunction "PA9_30") (pintype "bidirectional"))
    )
    (net (code "50") (name "GND") (class "Default")
      (node (ref "C1") (pin "1") (pinfunction "1_1") (pintype "passive"))
      (node (ref "C10") (pin "1") (pinfunction "1_1") (pintype "passive"))
      (node (ref "C11") (pin "1") (pinfunction "1_1") (pintype "passive"))
      (node (ref "C12") (pin "1") (pinfunction "1_1") (pintype "passive"))
      (node (ref "C13") (pin "2") (pinfunction "2_2") (pintype "passive"))
      (node (ref "C14") (pin "2") (pinfunction "2_2") (pintype "passive"))
      (node (ref "C15") (pin "1") (pinfunction "1_1") (pintype "passive"))
      (node (ref "C17") (pin "2") (pinfunction "2_2") (pintype "passive"))
      (node (ref "C18") (pin "2") (pinfunction "2_2") (pintype "passive"))
      (node (ref "C19") (pin "1") (pinfunction "1_1") (pintype "passive"))
      (node (ref "C2") (pin "1") (pinfunction "1_1") (pintype "passive"))
      (node (ref "C20") (pin "1") (pinfunction "1_1") (pintype "passive"))
      (node (ref "C21") (pin "1") (pinfunction "1_1") (pintype "passive"))
      (node (ref "C22") (pin "1") (pinfunction "1_1") (pintype "passive"))
      (node (ref "C23") (pin "1") (pinfunction "1_1") (pintype "passive"))
      (node (ref "C24") (pin "1") (pinfunction "1_1") (pintype "passive"))
      (node (ref "C25") (pin "2") (pinfunction "2_2") (pintype "passive"))
      (node (ref "C26") (pin "2") (pinfunction "2_2") (pintype "passive"))
      (node (ref "C27") (pin "2") (pinfunction "2_2") (pintype "passive"))
      (node (ref "C28") (pin "2") (pinfunction "2_2") (pintype "passive"))
      (node (ref "C29") (pin "1") (pinfunction "1_1") (pintype "passive"))
      (node (ref "C3") (pin "1") (pinfunction "1_1") (pintype "passive"))
      (node (ref "C30") (pin "1") (pinfunction "1_1") (pintype "passive"))
      (node (ref "C5") (pin "1") (pinfunction "1_1") (pintype "passive"))
      (node (ref "C6") (pin "1") (pinfunction "1_1") (pintype "passive"))
      (node (ref "C7") (pin "1") (pinfunction "1_1") (pintype "passive"))
      (node (ref "C9") (pin "2") (pinfunction "2_2") (pintype "passive"))
      (node (ref "D2") (pin "2") (pinfunction "A_2") (pintype "passive"))
      (node (ref "D3") (pin "2") (pinfunction "A_2") (pintype "passive"))
      (node (ref "J1") (pin "1") (pinfunction "DGND_1") (pintype "bidirectional"))
      (node (ref "J1") (pin "3") (pinfunction "IN_3") (pintype "bidirectional"))
      (node (ref "JP1") (pin "1") (pinfunction "1_1") (pintype "passive"))
      (node (ref "JP4") (pin "3") (pinfunction "3_3") (pintype "passive"))
      (node (ref "JP4") (pin "4") (pinfunction "4_4") (pintype "passive"))
      (node (ref "JP4") (pin "7") (pinfunction "7_7") (pintype "passive"))
      (node (ref "JP4") (pin "8") (pinfunction "8_8") (pintype "passive"))
      (node (ref "R12") (pin "1") (pinfunction "1_1") (pintype "passive"))
      (node (ref "R13") (pin "2") (pinfunction "2_2") (pintype "passive"))
      (node (ref "R14") (pin "1") (pinfunction "1_1") (pintype "passive"))
      (node (ref "R19") (pin "1") (pinfunction "1_1") (pintype "passive"))
      (node (ref "R20") (pin "1") (pinfunction "1_1") (pintype "passive"))
      (node (ref "R26") (pin "1") (pinfunction "1_1") (pintype "passive"))
      (node (ref "R27") (pin "1") (pinfunction "1_1") (pintype "passive"))
      (node (ref "R31") (pin "1") (pinfunction "1_1") (pintype "passive"))
      (node (ref "R33") (pin "1") (pinfunction "1_1") (pintype "passive"))
      (node (ref "R9") (pin "1") (pinfunction "1_1") (pintype "passive"))
      (node (ref "U$10") (pin "3") (pinfunction "GND_3") (pintype "power_in"))
      (node (ref "U$11") (pin "2") (pinfunction "GND_2") (pintype "power_in"))
      (node (ref "U$11") (pin "4") (pinfunction "GND1_4") (pintype "power_in"))
      (node (ref "U$12") (pin "5") (pinfunction "GND_5") (pintype "bidirectional"))
      (node (ref "U$12") (pin "6") (pinfunction "FILTER_6") (pintype "bidirectional"))
      (node (ref "U$2") (pin "P$3") (pinfunction "E_P$3") (pintype "bidirectional"))
      (node (ref "U$3") (pin "P$3") (pinfunction "E_P$3") (pintype "bidirectional"))
      (node (ref "U$5") (pin "47") (pinfunction "VSS_1_47") (pintype "bidirectional"))
      (node (ref "U$7") (pin "1") (pinfunction "1_1") (pintype "passive"))
      (node (ref "U$7") (pin "2") (pinfunction "2_2") (pintype "passive"))
      (node (ref "U$7") (pin "3") (pinfunction "3_3") (pintype "passive"))
      (node (ref "U$7") (pin "4") (pinfunction "4_4") (pintype "passive"))
      (node (ref "U1") (pin "3") (pinfunction "IN-_3") (pintype "bidirectional"))
      (node (ref "U1") (pin "4") (pinfunction "GND1_4") (pintype "bidirectional"))
      (node (ref "U2") (pin "3") (pinfunction "IN-_3") (pintype "bidirectional"))
      (node (ref "U2") (pin "4") (pinfunction "GND1_4") (pintype "bidirectional"))
      (node (ref "U2") (pin "8") (pinfunction "GND2_8") (pintype "bidirectional"))
      (node (ref "U3") (pin "3") (pinfunction "IN-_3") (pintype "bidirectional"))
      (node (ref "U3") (pin "4") (pinfunction "GND1_4") (pintype "bidirectional"))
      (node (ref "U3") (pin "8") (pinfunction "GND2_8") (pintype "bidirectional"))
      (node (ref "U4") (pin "3") (pinfunction "IN-_3") (pintype "bidirectional"))
      (node (ref "U4") (pin "4") (pinfunction "GND1_4") (pintype "bidirectional"))
      (node (ref "U5") (pin "N/C") (pinfunction "GND_N/C") (pintype "input"))
      (node (ref "U6") (pin "2") (pinfunction "GND_2") (pintype "passive"))
    )
    (net (code "51") (name "Net-(C29-Pad2)") (class "Default")
      (node (ref "C29") (pin "2") (pinfunction "2_2") (pintype "passive"))
      (node (ref "R28") (pin "2") (pinfunction "2_2") (pintype "passive"))
      (node (ref "R29") (pin "1") (pinfunction "1_1") (pintype "passive"))
    )
    (net (code "52") (name "Net-(D5-A)") (class "Default")
      (node (ref "D5") (pin "2") (pinfunction "A_2") (pintype "passive"))
      (node (ref "R23") (pin "1") (pinfunction "1_1") (pintype "passive"))
    )
    (net (code "53") (name "Net-(D6-A)") (class "Default")
      (node (ref "D6") (pin "2") (pinfunction "A_2") (pintype "passive"))
      (node (ref "R24") (pin "1") (pinfunction "1_1") (pintype "passive"))
    )
    (net (code "54") (name "Net-(LED1-PadC)") (class "Default")
      (node (ref "LED1") (pin "C") (pinfunction "C_C") (pintype "passive"))
      (node (ref "R19") (pin "2") (pinfunction "2_2") (pintype "passive"))
    )
    (net (code "55") (name "Net-(LED2-PadC)") (class "Default")
      (node (ref "LED2") (pin "C") (pinfunction "C_C") (pintype "passive"))
      (node (ref "R20") (pin "2") (pinfunction "2_2") (pintype "passive"))
    )
    (net (code "56") (name "Net-(LED3-PadC)") (class "Default")
      (node (ref "LED3") (pin "C") (pinfunction "C_C") (pintype "passive"))
      (node (ref "R21") (pin "2") (pinfunction "2_2") (pintype "passive"))
    )
    (net (code "57") (name "Net-(LED4-PadC)") (class "Default")
      (node (ref "LED4") (pin "C") (pinfunction "C_C") (pintype "passive"))
      (node (ref "R22") (pin "2") (pinfunction "2_2") (pintype "passive"))
    )
    (net (code "58") (name "Net-(R15-Pad1)") (class "Default")
      (node (ref "R15") (pin "1") (pinfunction "1_1") (pintype "passive"))
      (node (ref "SW1") (pin "2") (pinfunction "2_2") (pintype "passive"))
    )
    (net (code "59") (name "Net-(R16-Pad1)") (class "Default")
      (node (ref "R16") (pin "1") (pinfunction "1_1") (pintype "passive"))
      (node (ref "SW1") (pin "1") (pinfunction "1_1") (pintype "passive"))
    )
    (net (code "60") (name "Net-(R17-Pad1)") (class "Default")
      (node (ref "R17") (pin "1") (pinfunction "1_1") (pintype "passive"))
      (node (ref "SW2") (pin "2") (pinfunction "2_2") (pintype "passive"))
    )
    (net (code "61") (name "Net-(R18-Pad1)") (class "Default")
      (node (ref "R18") (pin "1") (pinfunction "1_1") (pintype "passive"))
      (node (ref "SW2") (pin "1") (pinfunction "1_1") (pintype "passive"))
    )
    (net (code "62") (name "Net-(TP1-1)") (class "Default")
      (node (ref "R1") (pin "2") (pinfunction "2_2") (pintype "passive"))
      (node (ref "R2") (pin "2") (pinfunction "2_2") (pintype "passive"))
      (node (ref "R9") (pin "2") (pinfunction "2_2") (pintype "passive"))
      (node (ref "TP1") (pin "P$1") (pinfunction "1_P$1") (pintype "bidirectional"))
      (node (ref "U$3") (pin "P$1") (pinfunction "G_P$1") (pintype "bidirectional"))
    )
    (net (code "63") (name "Net-(TP2-1)") (class "Default")
      (node (ref "R10") (pin "2") (pinfunction "2_2") (pintype "passive"))
      (node (ref "R3") (pin "2") (pinfunction "2_2") (pintype "passive"))
      (node (ref "R4") (pin "2") (pinfunction "2_2") (pintype "passive"))
      (node (ref "TP2") (pin "P$1") (pinfunction "1_P$1") (pintype "bidirectional"))
      (node (ref "U$1") (pin "P$1") (pinfunction "G_P$1") (pintype "bidirectional"))
    )
    (net (code "64") (name "Net-(TP3-1)") (class "Default")
      (node (ref "R11") (pin "2") (pinfunction "2_2") (pintype "passive"))
      (node (ref "R7") (pin "2") (pinfunction "2_2") (pintype "passive"))
      (node (ref "R8") (pin "2") (pinfunction "2_2") (pintype "passive"))
      (node (ref "TP3") (pin "P$1") (pinfunction "1_P$1") (pintype "bidirectional"))
      (node (ref "U$4") (pin "P$1") (pinfunction "G_P$1") (pintype "bidirectional"))
    )
    (net (code "65") (name "Net-(TP4-1)") (class "Default")
      (node (ref "R12") (pin "2") (pinfunction "2_2") (pintype "passive"))
      (node (ref "R5") (pin "2") (pinfunction "2_2") (pintype "passive"))
      (node (ref "R6") (pin "2") (pinfunction "2_2") (pintype "passive"))
      (node (ref "TP4") (pin "P$1") (pinfunction "1_P$1") (pintype "bidirectional"))
      (node (ref "U$2") (pin "P$1") (pinfunction "G_P$1") (pintype "bidirectional"))
    )
    (net (code "66") (name "Net-(TP15-1)") (class "Default")
      (node (ref "R13") (pin "1") (pinfunction "1_1") (pintype "passive"))
      (node (ref "TP15") (pin "P$1") (pinfunction "1_P$1") (pintype "bidirectional"))
      (node (ref "U$10") (pin "4") (pinfunction "DATA_4") (pintype "passive"))
      (node (ref "U$5") (pin "14") (pinfunction "PA4_14") (pintype "bidirectional"))
    )
    (net (code "67") (name "Net-(TP16-1)") (class "Default")
      (node (ref "TP16") (pin "P$1") (pinfunction "1_P$1") (pintype "bidirectional"))
      (node (ref "U$11") (pin "1") (pinfunction "DATA_1") (pintype "passive"))
      (node (ref "U$5") (pin "15") (pinfunction "PA5_15") (pintype "bidirectional"))
    )
    (net (code "68") (name "Net-(U$10-VCC)") (class "Default")
      (node (ref "C15") (pin "2") (pinfunction "2_2") (pintype "passive"))
      (node (ref "C19") (pin "2") (pinfunction "2_2") (pintype "passive"))
      (node (ref "L2") (pin "1") (pinfunction "1_1") (pintype "passive"))
      (node (ref "U$10") (pin "1") (pinfunction "VCC_1") (pintype "power_in"))
    )
    (net (code "69") (name "Net-(U$11-VCC)") (class "Default")
      (node (ref "C20") (pin "2") (pinfunction "2_2") (pintype "passive"))
      (node (ref "C21") (pin "2") (pinfunction "2_2") (pintype "passive"))
      (node (ref "L3") (pin "1") (pinfunction "1_1") (pintype "passive"))
      (node (ref "U$11") (pin "3") (pinfunction "VCC_3") (pintype "power_in"))
    )
    (net (code "70") (name "Net-(U1-OUT+)") (class "Default")
      (node (ref "R3") (pin "1") (pinfunction "1_1") (pintype "passive"))
      (node (ref "U1") (pin "6") (pinfunction "OUT+_6") (pintype "bidirectional"))
    )
    (net (code "71") (name "Net-(U1-OUT-)") (class "Default")
      (node (ref "R4") (pin "1") (pinfunction "1_1") (pintype "passive"))
      (node (ref "U1") (pin "7") (pinfunction "OUT-_7") (pintype "bidirectional"))
    )
    (net (code "72") (name "Net-(U1-VCC2)") (class "Default")
      (node (ref "C4") (pin "2") (pinfunction "2_2") (pintype "passive"))
      (node (ref "D5") (pin "1") (pinfunction "C_1") (pintype "passive"))
      (node (ref "D5") (pin "3") (pinfunction "C_3") (pintype "passive"))
      (node (ref "U1") (pin "5") (pinfunction "VCC2_5") (pintype "bidirectional"))
    )
    (net (code "73") (name "Net-(U2-OUT+)") (class "Default")
      (node (ref "R1") (pin "1") (pinfunction "1_1") (pintype "passive"))
      (node (ref "U2") (pin "6") (pinfunction "OUT+_6") (pintype "bidirectional"))
    )
    (net (code "74") (name "Net-(U2-OUT-)") (class "Default")
      (node (ref "R2") (pin "1") (pinfunction "1_1") (pintype "passive"))
      (node (ref "U2") (pin "7") (pinfunction "OUT-_7") (pintype "bidirectional"))
    )
    (net (code "75") (name "Net-(U3-OUT+)") (class "Default")
      (node (ref "R5") (pin "1") (pinfunction "1_1") (pintype "passive"))
      (node (ref "U3") (pin "6") (pinfunction "OUT+_6") (pintype "bidirectional"))
    )
    (net (code "76") (name "Net-(U3-OUT-)") (class "Default")
      (node (ref "R6") (pin "1") (pinfunction "1_1") (pintype "passive"))
      (node (ref "U3") (pin "7") (pinfunction "OUT-_7") (pintype "bidirectional"))
    )
    (net (code "77") (name "Net-(U4-OUT+)") (class "Default")
      (node (ref "R7") (pin "1") (pinfunction "1_1") (pintype "passive"))
      (node (ref "U4") (pin "6") (pinfunction "OUT+_6") (pintype "bidirectional"))
    )
    (net (code "78") (name "Net-(U4-OUT-)") (class "Default")
      (node (ref "R8") (pin "1") (pinfunction "1_1") (pintype "passive"))
      (node (ref "U4") (pin "7") (pinfunction "OUT-_7") (pintype "bidirectional"))
    )
    (net (code "79") (name "Net-(U4-VCC2)") (class "Default")
      (node (ref "C8") (pin "2") (pinfunction "2_2") (pintype "passive"))
      (node (ref "D6") (pin "1") (pinfunction "C_1") (pintype "passive"))
      (node (ref "D6") (pin "3") (pinfunction "C_3") (pintype "passive"))
      (node (ref "U4") (pin "5") (pinfunction "VCC2_5") (pintype "bidirectional"))
    )
    (net (code "80") (name "unconnected-(U5-BP-PadCOM)") (class "Default")
      (node (ref "U5") (pin "COM") (pinfunction "BP_COM") (pintype "input"))
    )
    (net (code "81") (name "unconnected-(U6-VREF-Pad5)") (class "Default")
      (node (ref "U6") (pin "5") (pinfunction "VREF_5") (pintype "output"))
    )
  )
)
